# watchplb_gps_v1_0_AB.net
KiCad netlist of a schematic drawn in EAGLE
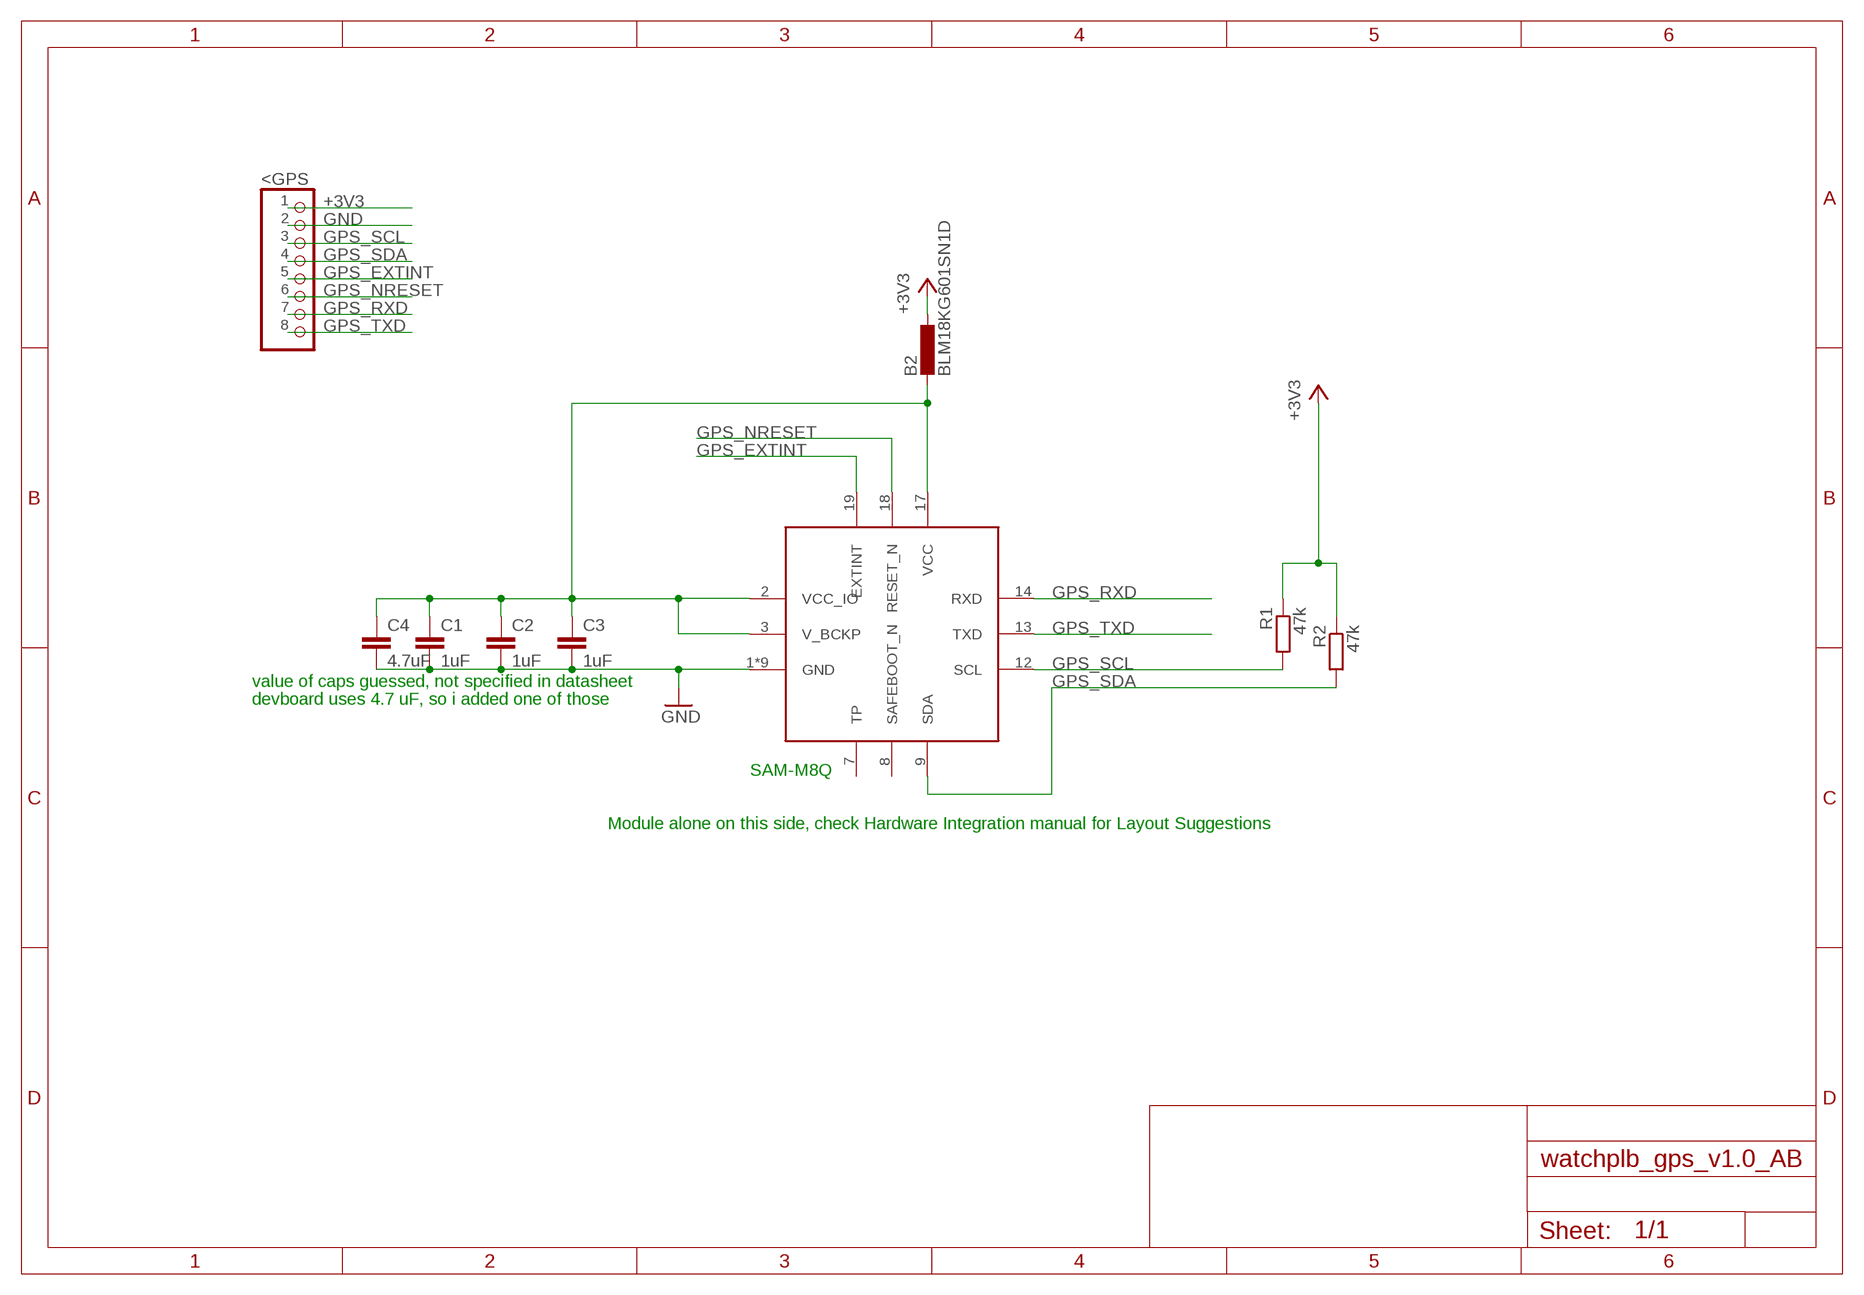
[diagram p0: schematic, sheet 1]

(export (version "E")
  (design (tool "Eeschema 10.0.6"))
  (components
    (comp (ref "<GPS")
      (value "PINHD-1X8")
      (footprint "eagle-import:1X08")
      (libsource (lib "eagle-import") (part "PINHD-1X8"))
    )
    (comp (ref "B2")
      (value "BLM18KG601SN1D")
      (footprint "eagle-import:L0603")
      (libsource (lib "eagle-import") (part "B-EU_B0603"))
    )
    (comp (ref "C1")
      (value "1uF")
      (footprint "eagle-import:C0805")
      (libsource (lib "eagle-import") (part "C-EUC0805"))
    )
    (comp (ref "C2")
      (value "1uF")
      (footprint "eagle-import:C0805")
      (libsource (lib "eagle-import") (part "C-EUC0805"))
    )
    (comp (ref "C3")
      (value "1uF")
      (footprint "eagle-import:C0805")
      (libsource (lib "eagle-import") (part "C-EUC0805"))
    )
    (comp (ref "C4")
      (value "4.7uF")
      (footprint "eagle-import:C0805")
      (libsource (lib "eagle-import") (part "C-EUC0805"))
    )
    (comp (ref "IC1")
      (value "SAM-M8Q")
      (footprint "eagle-import:SAM-M8Q")
      (libsource (lib "eagle-import") (part "SAM-M8Q"))
    )
    (comp (ref "R1")
      (value "47k")
      (footprint "eagle-import:M0805")
      (libsource (lib "eagle-import") (part "R-EU_M0805"))
    )
    (comp (ref "R2")
      (value "47k")
      (footprint "eagle-import:M0805")
      (libsource (lib "eagle-import") (part "R-EU_M0805"))
    )
  )
  (nets
    (net (code "1") (name "+3V3") (class "Default")
      (node (ref "<GPS") (pin "1") (pinfunction "1_1") (pintype "passive"))
      (node (ref "B2") (pin "1") (pinfunction "1_1") (pintype "passive"))
      (node (ref "R1") (pin "1") (pinfunction "1_1") (pintype "passive"))
      (node (ref "R2") (pin "1") (pinfunction "1_1") (pintype "passive"))
    )
    (net (code "2") (name "/GPS_EXTINT") (class "Default")
      (node (ref "<GPS") (pin "5") (pinfunction "5_5") (pintype "passive"))
      (node (ref "IC1") (pin "19") (pinfunction "EXTINT_19") (pintype "bidirectional"))
    )
    (net (code "3") (name "/GPS_NRESET") (class "Default")
      (node (ref "<GPS") (pin "6") (pinfunction "6_6") (pintype "passive"))
      (node (ref "IC1") (pin "18") (pinfunction "RESET_N_18") (pintype "bidirectional"))
    )
    (net (code "4") (name "/GPS_RXD") (class "Default")
      (node (ref "<GPS") (pin "7") (pinfunction "7_7") (pintype "passive"))
      (node (ref "IC1") (pin "14") (pinfunction "RXD_14") (pintype "bidirectional"))
    )
    (net (code "5") (name "/GPS_SCL") (class "Default")
      (node (ref "<GPS") (pin "3") (pinfunction "3_3") (pintype "passive"))
      (node (ref "IC1") (pin "12") (pinfunction "SCL_12") (pintype "bidirectional"))
      (node (ref "R1") (pin "2") (pinfunction "2_2") (pintype "passive"))
    )
    (net (code "6") (name "/GPS_SDA") (class "Default")
      (node (ref "<GPS") (pin "4") (pinfunction "4_4") (pintype "passive"))
      (node (ref "IC1") (pin "9") (pinfunction "SDA_9") (pintype "bidirectional"))
      (node (ref "R2") (pin "2") (pinfunction "2_2") (pintype "passive"))
    )
    (net (code "7") (name "/GPS_TXD") (class "Default")
      (node (ref "<GPS") (pin "8") (pinfunction "8_8") (pintype "passive"))
      (node (ref "IC1") (pin "13") (pinfunction "TXD_13") (pintype "bidirectional"))
    )
    (net (code "8") (name "GND") (class "Default")
      (node (ref "<GPS") (pin "2") (pinfunction "2_2") (pintype "passive"))
      (node (ref "C1") (pin "2") (pinfunction "2_2") (pintype "passive"))
      (node (ref "C2") (pin "2") (pinfunction "2_2") (pintype "passive"))
      (node (ref "C3") (pin "2") (pinfunction "2_2") (pintype "passive"))
      (node (ref "C4") (pin "2") (pinfunction "2_2") (pintype "passive"))
      (node (ref "IC1") (pin "1") (pinfunction "GND_1") (pintype "bidirectional"))
      (node (ref "IC1") (pin "10") (pinfunction "GND_10") (pintype "bidirectional"))
      (node (ref "IC1") (pin "11") (pinfunction "GND_11") (pintype "bidirectional"))
      (node (ref "IC1") (pin "15") (pinfunction "GND_15") (pintype "bidirectional"))
      (node (ref "IC1") (pin "16") (pinfunction "GND_16") (pintype "bidirectional"))
      (node (ref "IC1") (pin "20") (pinfunction "GND_20") (pintype "bidirectional"))
      (node (ref "IC1") (pin "4") (pinfunction "GND_4") (pintype "bidirectional"))
      (node (ref "IC1") (pin "5") (pinfunction "GND_5") (pintype "bidirectional"))
      (node (ref "IC1") (pin "6") (pinfunction "GND_6") (pintype "bidirectional"))
    )
    (net (code "9") (name "Net-(IC1-VCC)") (class "Default")
      (node (ref "B2") (pin "2") (pinfunction "2_2") (pintype "passive"))
      (node (ref "C1") (pin "1") (pinfunction "1_1") (pintype "passive"))
      (node (ref "C2") (pin "1") (pinfunction "1_1") (pintype "passive"))
      (node (ref "C3") (pin "1") (pinfunction "1_1") (pintype "passive"))
      (node (ref "C4") (pin "1") (pinfunction "1_1") (pintype "passive"))
      (node (ref "IC1") (pin "17") (pinfunction "VCC_17") (pintype "bidirectional"))
      (node (ref "IC1") (pin "2") (pinfunction "VCC_IO_2") (pintype "bidirectional"))
      (node (ref "IC1") (pin "3") (pinfunction "V_BCKP_3") (pintype "bidirectional"))
    )
    (net (code "10") (name "unconnected-(IC1-SAFEBOOT_N-Pad8)") (class "Default")
      (node (ref "IC1") (pin "8") (pinfunction "SAFEBOOT_N_8") (pintype "bidirectional"))
    )
    (net (code "11") (name "unconnected-(IC1-TP-Pad7)") (class "Default")
      (node (ref "IC1") (pin "7") (pinfunction "TP_7") (pintype "bidirectional"))
    )
  )
)
